# ST_LINK_V2.net
KiCad netlist of a schematic drawn in Altium Designer
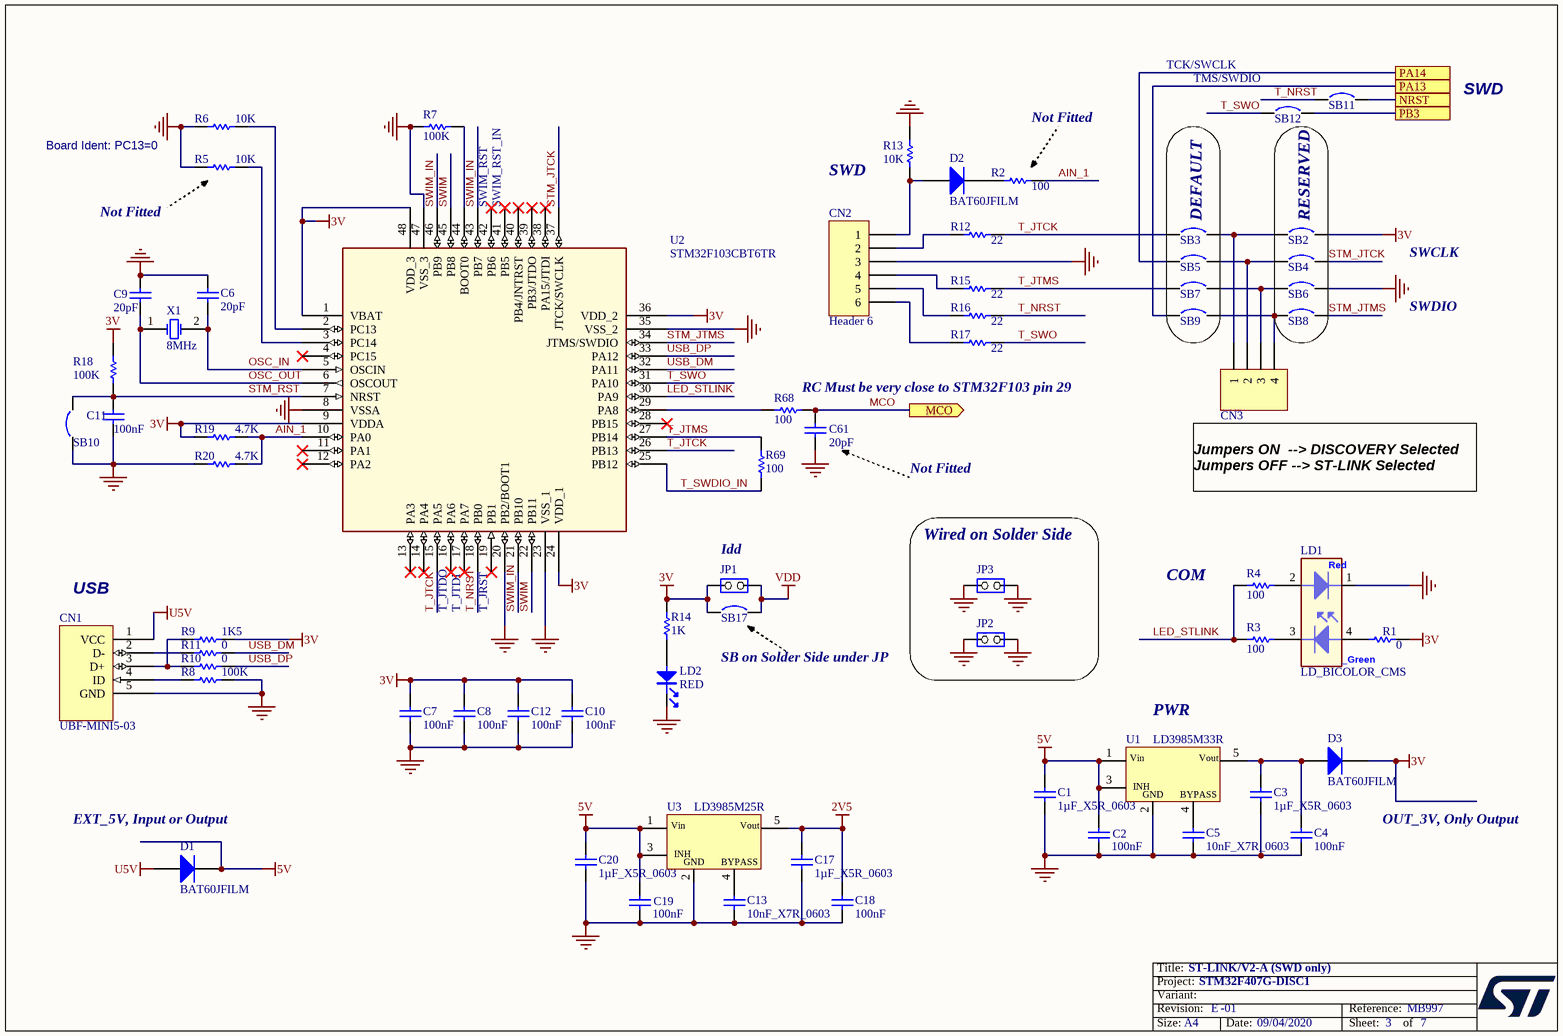
[diagram p0: ST_LINK_V2.SCHDOC]

(export (version "E")
  (design (tool "Eeschema 10.0.6"))
  (components
    (comp (ref "C1")
      (value "1µF_X5R_0603")
      (footprint "0603C")
      (description "0603  X5R 1µF")
      (fields (field (name "TOLERANCE") "10%"))
      (libsource (lib "MB963_1") (part "CAP SMD 0603  X5R 1µF 25V 10%"))
    )
    (comp (ref "C2")
      (value "100nF")
      (footprint "0402C")
      (description "Capacitor")
      (fields (field (name "PUBLISHER") "Altium Limited"))
      (libsource (lib "MB915_1") (part "Cap"))
    )
    (comp (ref "C3")
      (value "1µF_X5R_0603")
      (footprint "0603C")
      (description "0603  X5R 1µF")
      (fields (field (name "TOLERANCE") "10%"))
      (libsource (lib "MB963_1") (part "CAP SMD 0603  X5R 1µF 25V 10%"))
    )
    (comp (ref "C4")
      (value "100nF")
      (footprint "0402C")
      (description "Capacitor")
      (fields (field (name "PUBLISHER") "Altium Limited"))
      (libsource (lib "MB915_1") (part "Cap"))
    )
    (comp (ref "C5")
      (value "10nF_X7R_0603")
      (footprint "0603C")
      (description "0603  X7R 10NF")
      (fields (field (name "TOLERANCE") "10%"))
      (libsource (lib "MB963_1") (part "CAP SMD 0603  X7R 10000PF 50V 10%"))
    )
    (comp (ref "C6")
      (value "20pF")
      (footprint "0402C")
      (description "Capacitor")
      (fields (field (name "PUBLISHER") "Altium Limited"))
      (libsource (lib "MB915_1") (part "Cap"))
    )
    (comp (ref "C7")
      (value "100nF")
      (footprint "0402C")
      (description "Capacitor")
      (fields (field (name "PUBLISHER") "Altium Limited"))
      (libsource (lib "MB915_1") (part "Cap"))
    )
    (comp (ref "C8")
      (value "100nF")
      (footprint "0402C")
      (description "Capacitor")
      (fields (field (name "PUBLISHER") "Altium Limited"))
      (libsource (lib "MB915_1") (part "Cap"))
    )
    (comp (ref "C9")
      (value "20pF")
      (footprint "0402C")
      (description "Capacitor")
      (fields (field (name "PUBLISHER") "Altium Limited"))
      (libsource (lib "MB915_1") (part "Cap"))
    )
    (comp (ref "C10")
      (value "100nF")
      (footprint "0402C")
      (description "Capacitor")
      (fields (field (name "PUBLISHER") "Altium Limited"))
      (libsource (lib "MB915_1") (part "Cap"))
    )
    (comp (ref "C11")
      (value "100nF")
      (footprint "0402C")
      (description "Capacitor")
      (fields (field (name "PUBLISHER") "Altium Limited"))
      (libsource (lib "MB915_1") (part "Cap"))
    )
    (comp (ref "C12")
      (value "100nF")
      (footprint "0402C")
      (description "Capacitor")
      (fields (field (name "PUBLISHER") "Altium Limited"))
      (libsource (lib "MB915_1") (part "Cap"))
    )
    (comp (ref "C13")
      (value "10nF_X7R_0603")
      (footprint "0603C")
      (description "0603  X7R 10NF")
      (fields (field (name "TOLERANCE") "10%"))
      (libsource (lib "MB963_1") (part "CAP SMD 0603  X7R 10000PF 50V 10%"))
    )
    (comp (ref "C17")
      (value "1µF_X5R_0603")
      (footprint "0603C")
      (description "0603  X5R 1µF")
      (fields (field (name "TOLERANCE") "10%"))
      (libsource (lib "MB963_1") (part "CAP SMD 0603  X5R 1µF 25V 10%"))
    )
    (comp (ref "C18")
      (value "100nF")
      (footprint "0402C")
      (description "Capacitor")
      (fields (field (name "PUBLISHER") "Altium Limited"))
      (libsource (lib "MB915_1") (part "Cap"))
    )
    (comp (ref "C19")
      (value "100nF")
      (footprint "0402C")
      (description "Capacitor")
      (fields (field (name "PUBLISHER") "Altium Limited"))
      (libsource (lib "MB915_1") (part "Cap"))
    )
    (comp (ref "C20")
      (value "1µF_X5R_0603")
      (footprint "0603C")
      (description "0603  X5R 1µF")
      (fields (field (name "TOLERANCE") "10%"))
      (libsource (lib "MB963_1") (part "CAP SMD 0603  X5R 1µF 25V 10%"))
    )
    (comp (ref "C61")
      (value "20pF")
      (footprint "0603C")
      (description "Capacitor")
      (fields (field (name "PUBLISHER") "Altium Limited"))
      (libsource (lib "MB915_1") (part "Cap"))
    )
    (comp (ref "CN1")
      (value "UBF-MINI5-03")
      (footprint "USB-MINI-B-SMD-A_")
      (libsource (lib "MB997") (part "USB-MINI-typeB connector_"))
    )
    (comp (ref "CN2")
      (value "Header 6")
      (footprint "HEADER6$2F$2.54")
      (description "Header, 6-Pin")
      (fields (field (name "PUBLISHER") "Altium Limited"))
      (libsource (lib "Miscellaneous Connectors") (part "Header 6"))
    )
    (comp (ref "CN3")
      (value "Header 4")
      (footprint "HEADER4$2F$2.54")
      (description "Header, 4-Pin")
      (fields (field (name "PUBLISHER") "Altium Limited"))
      (libsource (lib "MB963_1") (part "Header 4"))
    )
    (comp (ref "D1")
      (value "BAT60JFILM")
      (footprint "SOD323$2F$A")
      (fields (field (name "PUBLISHER") "Altium Limited"))
      (libsource (lib "MB997") (part "BAT60JFILM"))
    )
    (comp (ref "D2")
      (value "BAT60JFILM")
      (footprint "SOD323$2F$A")
      (fields (field (name "PUBLISHER") "Altium Limited"))
      (libsource (lib "MB997") (part "BAT60JFILM"))
    )
    (comp (ref "D3")
      (value "BAT60JFILM")
      (footprint "SOD323$2F$A")
      (fields (field (name "PUBLISHER") "Altium Limited"))
      (libsource (lib "MB997") (part "BAT60JFILM"))
    )
    (comp (ref "JP1") (value "~") (footprint "SIP2$2F$2.54") (libsource (lib "*") (part "JP2")))
    (comp (ref "JP2") (value "~") (footprint "SIP2$2F$2.54") (libsource (lib "*") (part "JP2")))
    (comp (ref "JP3") (value "~") (footprint "SIP2$2F$2.54") (libsource (lib "*") (part "JP2")))
    (comp (ref "LD1")
      (value "LD_BICOLOR_CMS")
      (footprint "AV02-0501EN")
      (description "Bicolor Led")
      (libsource (lib "MB963") (part "LD_BICOLOR_CMS"))
    )
    (comp (ref "LD2") (value "RED") (footprint "LED0603") (libsource (lib "MB963_1") (part "PHOTO")))
    (comp (ref "R1")
      (value "0")
      (footprint "0603R")
      (description "Resistor")
      (fields (field (name "PUBLISHER") "Altium Limited"))
      (libsource (lib "MB915_1") (part "res1"))
    )
    (comp (ref "R2")
      (value "100")
      (footprint "0402R")
      (description "Resistor")
      (fields (field (name "PUBLISHER") "Altium Limited"))
      (libsource (lib "MB915_1") (part "res1"))
    )
    (comp (ref "R3")
      (value "100")
      (footprint "0402R")
      (description "Resistor")
      (fields (field (name "PUBLISHER") "Altium Limited"))
      (libsource (lib "MB915_1") (part "res1"))
    )
    (comp (ref "R4")
      (value "100")
      (footprint "0402R")
      (description "Resistor")
      (fields (field (name "PUBLISHER") "Altium Limited"))
      (libsource (lib "MB915_1") (part "res1"))
    )
    (comp (ref "R5")
      (value "10K")
      (footprint "0402R")
      (description "Resistor")
      (fields (field (name "PUBLISHER") "Altium Limited"))
      (libsource (lib "MB915_1") (part "res1"))
    )
    (comp (ref "R6")
      (value "10K")
      (footprint "0402R")
      (description "Resistor")
      (fields (field (name "PUBLISHER") "Altium Limited"))
      (libsource (lib "MB915_1") (part "res1"))
    )
    (comp (ref "R7")
      (value "100K")
      (footprint "0402R")
      (description "Resistor")
      (fields (field (name "PUBLISHER") "Altium Limited"))
      (libsource (lib "MB915_1") (part "res1"))
    )
    (comp (ref "R8")
      (value "100K")
      (footprint "0402R")
      (description "Resistor")
      (fields (field (name "PUBLISHER") "Altium Limited"))
      (libsource (lib "MB915_1") (part "res1"))
    )
    (comp (ref "R9")
      (value "1K5")
      (footprint "0402R")
      (description "Resistor")
      (fields (field (name "PUBLISHER") "Altium Limited"))
      (libsource (lib "MB915_1") (part "res1"))
    )
    (comp (ref "R10")
      (value "0")
      (footprint "0603R")
      (description "Resistor")
      (fields (field (name "PUBLISHER") "Altium Limited"))
      (libsource (lib "MB915_1") (part "res1"))
    )
    (comp (ref "R11")
      (value "0")
      (footprint "0603R")
      (description "Resistor")
      (fields (field (name "PUBLISHER") "Altium Limited"))
      (libsource (lib "MB915_1") (part "res1"))
    )
    (comp (ref "R12")
      (value "22")
      (footprint "0402R")
      (description "Resistor")
      (fields (field (name "PUBLISHER") "Altium Limited"))
      (libsource (lib "MB915_1") (part "res1"))
    )
    (comp (ref "R13")
      (value "10K")
      (footprint "0402R")
      (description "Resistor")
      (fields (field (name "PUBLISHER") "Altium Limited"))
      (libsource (lib "MB915_1") (part "res1"))
    )
    (comp (ref "R14")
      (value "1K")
      (footprint "0402R")
      (description "Resistor")
      (fields (field (name "PUBLISHER") "Altium Limited"))
      (libsource (lib "MB915_1") (part "res1"))
    )
    (comp (ref "R15")
      (value "22")
      (footprint "0402R")
      (description "Resistor")
      (fields (field (name "PUBLISHER") "Altium Limited"))
      (libsource (lib "MB915_1") (part "res1"))
    )
    (comp (ref "R16")
      (value "22")
      (footprint "0402R")
      (description "Resistor")
      (fields (field (name "PUBLISHER") "Altium Limited"))
      (libsource (lib "MB915_1") (part "res1"))
    )
    (comp (ref "R17")
      (value "22")
      (footprint "0402R")
      (description "Resistor")
      (fields (field (name "PUBLISHER") "Altium Limited"))
      (libsource (lib "MB915_1") (part "res1"))
    )
    (comp (ref "R18")
      (value "100K")
      (footprint "0402R")
      (description "Resistor")
      (fields (field (name "PUBLISHER") "Altium Limited"))
      (libsource (lib "MB915_1") (part "res1"))
    )
    (comp (ref "R19")
      (value "4.7K")
      (footprint "0402R")
      (description "Resistor")
      (fields (field (name "PUBLISHER") "Altium Limited"))
      (libsource (lib "MB915_1") (part "res1"))
    )
    (comp (ref "R20")
      (value "4.7K")
      (footprint "0402R")
      (description "Resistor")
      (fields (field (name "PUBLISHER") "Altium Limited"))
      (libsource (lib "MB915_1") (part "res1"))
    )
    (comp (ref "R68")
      (value "100")
      (footprint "0603R")
      (description "Resistor")
      (fields (field (name "PUBLISHER") "Altium Limited"))
      (libsource (lib "MB915_1") (part "res1"))
    )
    (comp (ref "R69")
      (value "100")
      (footprint "0402R")
      (description "Resistor")
      (fields (field (name "PUBLISHER") "Altium Limited"))
      (libsource (lib "MB915_1") (part "res1"))
    )
    (comp (ref "SB2")
      (value "Circuit Breaker")
      (footprint "JUMPER")
      (fields (field (name "PUBLISHER") "Altium Limited"))
      (libsource (lib "MB915") (part "Circuit Breaker"))
    )
    (comp (ref "SB3")
      (value "Circuit Breaker")
      (footprint "JUMPER")
      (fields (field (name "PUBLISHER") "Altium Limited"))
      (libsource (lib "MB915") (part "Circuit Breaker"))
    )
    (comp (ref "SB4")
      (value "Circuit Breaker")
      (footprint "JUMPER")
      (fields (field (name "PUBLISHER") "Altium Limited"))
      (libsource (lib "MB915") (part "Circuit Breaker"))
    )
    (comp (ref "SB5")
      (value "Circuit Breaker")
      (footprint "JUMPER")
      (fields (field (name "PUBLISHER") "Altium Limited"))
      (libsource (lib "MB915") (part "Circuit Breaker"))
    )
    (comp (ref "SB6")
      (value "Circuit Breaker")
      (footprint "JUMPER")
      (fields (field (name "PUBLISHER") "Altium Limited"))
      (libsource (lib "MB915") (part "Circuit Breaker"))
    )
    (comp (ref "SB7")
      (value "Circuit Breaker")
      (footprint "JUMPER")
      (fields (field (name "PUBLISHER") "Altium Limited"))
      (libsource (lib "MB915") (part "Circuit Breaker"))
    )
    (comp (ref "SB8")
      (value "Circuit Breaker")
      (footprint "JUMPER")
      (fields (field (name "PUBLISHER") "Altium Limited"))
      (libsource (lib "MB915") (part "Circuit Breaker"))
    )
    (comp (ref "SB9")
      (value "Circuit Breaker")
      (footprint "JUMPER")
      (fields (field (name "PUBLISHER") "Altium Limited"))
      (libsource (lib "MB915") (part "Circuit Breaker"))
    )
    (comp (ref "SB10")
      (value "Circuit Breaker")
      (footprint "JUMPER")
      (fields (field (name "PUBLISHER") "Altium Limited"))
      (libsource (lib "MB915") (part "Circuit Breaker"))
    )
    (comp (ref "SB11")
      (value "Circuit Breaker")
      (footprint "JUMPER")
      (fields (field (name "PUBLISHER") "Altium Limited"))
      (libsource (lib "MB915") (part "Circuit Breaker"))
    )
    (comp (ref "SB12")
      (value "Circuit Breaker")
      (footprint "JUMPER")
      (fields (field (name "PUBLISHER") "Altium Limited"))
      (libsource (lib "MB915") (part "Circuit Breaker"))
    )
    (comp (ref "SB17")
      (value "Circuit Breaker")
      (footprint "JUMPER")
      (fields (field (name "PUBLISHER") "Altium Limited"))
      (libsource (lib "MB915") (part "Circuit Breaker"))
    )
    (comp (ref "U1")
      (value "LD3985M33R")
      (footprint "SOT-23-5L")
      (description "Ultra low drop-low noise BiCMOS voltage, regulators low ESR capacitors compatible")
      (libsource (lib "MB997") (part "LD3985M33R"))
    )
    (comp (ref "U2")
      (value "STM32F103CBT6TR")
      (footprint "LQFP48$2F$0.5MM$5C$9X9B")
      (description "Medium-density performance line ARM-based 32-bit MCU with 128KB Flash")
      (libsource (lib "MCD_TOOLS") (part "STM32F103CBT6"))
    )
    (comp (ref "U3")
      (value "LD3985M25R")
      (footprint "SOT-23-5L")
      (description "Ultra low drop-low noise BiCMOS voltage, regulators low ESR capacitors compatible")
      (libsource (lib "MB997") (part "LD3985M25R"))
    )
    (comp (ref "X1")
      (value "8MHz")
      (footprint "HC-49A")
      (description "Crystal Oscillator")
      (fields (field (name "PUBLISHER") "Altium Limited"))
      (libsource (lib "MB963_1") (part "XTAL"))
    )
  )
  (nets
    (net (code "1") (name "/AIN_1") (class "Default")
      (node (ref "R19") (pin "2") (pinfunction "2_2") (pintype "passive"))
      (node (ref "R2") (pin "2") (pinfunction "2_2") (pintype "passive"))
      (node (ref "R20") (pin "2") (pinfunction "2_2") (pintype "passive"))
      (node (ref "U2") (pin "10") (pinfunction "PA0_10") (pintype "bidirectional"))
    )
    (net (code "2") (name "/LED_STLINK") (class "Default")
      (node (ref "R3") (pin "1") (pinfunction "1_1") (pintype "passive"))
      (node (ref "R4") (pin "1") (pinfunction "1_1") (pintype "passive"))
      (node (ref "U2") (pin "30") (pinfunction "PA9_30") (pintype "bidirectional"))
    )
    (net (code "3") (name "/MCO") (class "Default")
      (node (ref "C61") (pin "1") (pinfunction "1_1") (pintype "passive"))
      (node (ref "R68") (pin "2") (pinfunction "2_2") (pintype "passive"))
    )
    (net (code "4") (name "/NRST") (class "Default")
      (node (ref "SB11") (pin "2") (pinfunction "2_2") (pintype "passive"))
    )
    (net (code "5") (name "/OSC_IN") (class "Default")
      (node (ref "C6") (pin "2") (pinfunction "2_2") (pintype "passive"))
      (node (ref "U2") (pin "5") (pinfunction "OSCIN_5") (pintype "input"))
      (node (ref "X1") (pin "2") (pinfunction "OSC2_2") (pintype "passive"))
    )
    (net (code "6") (name "/OSC_OUT") (class "Default")
      (node (ref "C9") (pin "2") (pinfunction "2_2") (pintype "passive"))
      (node (ref "U2") (pin "6") (pinfunction "OSCOUT_6") (pintype "output"))
      (node (ref "X1") (pin "1") (pinfunction "OSC1_1") (pintype "passive"))
    )
    (net (code "7") (name "/PA13") (class "Default")
      (node (ref "SB9") (pin "1") (pinfunction "1_1") (pintype "passive"))
    )
    (net (code "8") (name "/PA14") (class "Default")
      (node (ref "SB5") (pin "1") (pinfunction "1_1") (pintype "passive"))
    )
    (net (code "9") (name "/PB3") (class "Default")
      (node (ref "SB12") (pin "2") (pinfunction "2_2") (pintype "passive"))
    )
    (net (code "10") (name "/STM_JTCK") (class "Default")
      (node (ref "SB4") (pin "2") (pinfunction "2_2") (pintype "passive"))
      (node (ref "U2") (pin "37") (pinfunction "JTCK/SWCLK_37") (pintype "bidirectional"))
    )
    (net (code "11") (name "/STM_JTMS") (class "Default")
      (node (ref "SB8") (pin "2") (pinfunction "2_2") (pintype "passive"))
      (node (ref "U2") (pin "34") (pinfunction "JTMS/SWDIO_34") (pintype "bidirectional"))
    )
    (net (code "12") (name "/STM_RST") (class "Default")
      (node (ref "C11") (pin "2") (pinfunction "2_2") (pintype "passive"))
      (node (ref "R18") (pin "1") (pinfunction "1_1") (pintype "passive"))
      (node (ref "SB10") (pin "2") (pinfunction "2_2") (pintype "passive"))
      (node (ref "U2") (pin "7") (pinfunction "NRST_7") (pintype "input"))
    )
    (net (code "13") (name "/SWIM") (class "Default")
      (node (ref "U2") (pin "22") (pinfunction "PB11_22") (pintype "bidirectional"))
      (node (ref "U2") (pin "45") (pinfunction "PB8_45") (pintype "bidirectional"))
    )
    (net (code "14") (name "/SWIM_IN") (class "Default")
      (node (ref "U2") (pin "21") (pinfunction "PB10_21") (pintype "bidirectional"))
      (node (ref "U2") (pin "43") (pinfunction "PB7_43") (pintype "bidirectional"))
      (node (ref "U2") (pin "46") (pinfunction "PB9_46") (pintype "bidirectional"))
    )
    (net (code "15") (name "/T_JTCK") (class "Default")
      (node (ref "R12") (pin "2") (pinfunction "2_2") (pintype "passive"))
      (node (ref "SB3") (pin "1") (pinfunction "1_1") (pintype "passive"))
      (node (ref "U2") (pin "15") (pinfunction "PA5_15") (pintype "bidirectional"))
      (node (ref "U2") (pin "26") (pinfunction "PB13_26") (pintype "bidirectional"))
    )
    (net (code "16") (name "/T_JTMS") (class "Default")
      (node (ref "R15") (pin "2") (pinfunction "2_2") (pintype "passive"))
      (node (ref "R69") (pin "2") (pinfunction "2_2") (pintype "passive"))
      (node (ref "SB7") (pin "1") (pinfunction "1_1") (pintype "passive"))
      (node (ref "U2") (pin "27") (pinfunction "PB14_27") (pintype "bidirectional"))
    )
    (net (code "17") (name "/T_NRST") (class "Default")
      (node (ref "R16") (pin "2") (pinfunction "2_2") (pintype "passive"))
      (node (ref "SB11") (pin "1") (pinfunction "1_1") (pintype "passive"))
      (node (ref "U2") (pin "18") (pinfunction "PB0_18") (pintype "bidirectional"))
    )
    (net (code "18") (name "/T_SWDIO_IN") (class "Default")
      (node (ref "R69") (pin "1") (pinfunction "1_1") (pintype "passive"))
      (node (ref "U2") (pin "25") (pinfunction "PB12_25") (pintype "bidirectional"))
    )
    (net (code "19") (name "/T_SWO") (class "Default")
      (node (ref "R17") (pin "2") (pinfunction "2_2") (pintype "passive"))
      (node (ref "SB12") (pin "1") (pinfunction "1_1") (pintype "passive"))
      (node (ref "U2") (pin "31") (pinfunction "PA10_31") (pintype "bidirectional"))
    )
    (net (code "20") (name "/USB_DM") (class "Default")
      (node (ref "R11") (pin "2") (pinfunction "2_2") (pintype "passive"))
      (node (ref "U2") (pin "32") (pinfunction "PA11_32") (pintype "bidirectional"))
    )
    (net (code "21") (name "/USB_DP") (class "Default")
      (node (ref "R10") (pin "2") (pinfunction "2_2") (pintype "passive"))
      (node (ref "U2") (pin "33") (pinfunction "PA12_33") (pintype "bidirectional"))
    )
    (net (code "22") (name "2V5") (class "Default")
      (node (ref "C17") (pin "1") (pinfunction "1_1") (pintype "passive"))
      (node (ref "C18") (pin "2") (pinfunction "2_2") (pintype "passive"))
      (node (ref "U3") (pin "5") (pinfunction "Vout_5") (pintype "passive"))
    )
    (net (code "23") (name "3V") (class "Default")
      (node (ref "C10") (pin "2") (pinfunction "2_2") (pintype "passive"))
      (node (ref "C12") (pin "1") (pinfunction "1_1") (pintype "passive"))
      (node (ref "C7") (pin "2") (pinfunction "2_2") (pintype "passive"))
      (node (ref "C8") (pin "2") (pinfunction "2_2") (pintype "passive"))
      (node (ref "D3") (pin "2") (pinfunction "K_2") (pintype "passive"))
      (node (ref "JP1") (pin "1") (pinfunction "COMMON_1") (pintype "passive"))
      (node (ref "R1") (pin "2") (pinfunction "2_2") (pintype "passive"))
      (node (ref "R14") (pin "2") (pinfunction "2_2") (pintype "passive"))
      (node (ref "R18") (pin "2") (pinfunction "2_2") (pintype "passive"))
      (node (ref "R19") (pin "1") (pinfunction "1_1") (pintype "passive"))
      (node (ref "R9") (pin "2") (pinfunction "2_2") (pintype "passive"))
      (node (ref "SB17") (pin "1") (pinfunction "1_1") (pintype "passive"))
      (node (ref "SB2") (pin "2") (pinfunction "2_2") (pintype "passive"))
      (node (ref "U2") (pin "1") (pinfunction "VBAT_1") (pintype "power_in"))
      (node (ref "U2") (pin "24") (pinfunction "VDD_1_24") (pintype "power_in"))
      (node (ref "U2") (pin "36") (pinfunction "VDD_2_36") (pintype "power_in"))
      (node (ref "U2") (pin "48") (pinfunction "VDD_3_48") (pintype "power_in"))
      (node (ref "U2") (pin "9") (pinfunction "VDDA_9") (pintype "power_in"))
    )
    (net (code "24") (name "5V") (class "Default")
      (node (ref "C1") (pin "2") (pinfunction "2_2") (pintype "passive"))
      (node (ref "C19") (pin "2") (pinfunction "2_2") (pintype "passive"))
      (node (ref "C2") (pin "2") (pinfunction "2_2") (pintype "passive"))
      (node (ref "C20") (pin "2") (pinfunction "2_2") (pintype "passive"))
      (node (ref "D1") (pin "2") (pinfunction "K_2") (pintype "passive"))
      (node (ref "U1") (pin "1") (pinfunction "Vin_1") (pintype "passive"))
      (node (ref "U1") (pin "3") (pinfunction "CE_3") (pintype "passive"))
      (node (ref "U3") (pin "1") (pinfunction "Vin_1") (pintype "passive"))
      (node (ref "U3") (pin "3") (pinfunction "CE_3") (pintype "passive"))
    )
    (net (code "25") (name "GND") (class "Default")
      (node (ref "C1") (pin "1") (pinfunction "1_1") (pintype "passive"))
      (node (ref "C10") (pin "1") (pinfunction "1_1") (pintype "passive"))
      (node (ref "C11") (pin "1") (pinfunction "1_1") (pintype "passive"))
      (node (ref "C12") (pin "2") (pinfunction "2_2") (pintype "passive"))
      (node (ref "C13") (pin "1") (pinfunction "1_1") (pintype "passive"))
      (node (ref "C17") (pin "2") (pinfunction "2_2") (pintype "passive"))
      (node (ref "C18") (pin "1") (pinfunction "1_1") (pintype "passive"))
      (node (ref "C19") (pin "1") (pinfunction "1_1") (pintype "passive"))
      (node (ref "C2") (pin "1") (pinfunction "1_1") (pintype "passive"))
      (node (ref "C20") (pin "1") (pinfunction "1_1") (pintype "passive"))
      (node (ref "C3") (pin "2") (pinfunction "2_2") (pintype "passive"))
      (node (ref "C4") (pin "1") (pinfunction "1_1") (pintype "passive"))
      (node (ref "C5") (pin "1") (pinfunction "1_1") (pintype "passive"))
      (node (ref "C6") (pin "1") (pinfunction "1_1") (pintype "passive"))
      (node (ref "C61") (pin "2") (pinfunction "2_2") (pintype "passive"))
      (node (ref "C7") (pin "1") (pinfunction "1_1") (pintype "passive"))
      (node (ref "C8") (pin "1") (pinfunction "1_1") (pintype "passive"))
      (node (ref "C9") (pin "1") (pinfunction "1_1") (pintype "passive"))
      (node (ref "CN1") (pin "5") (pinfunction "GND_5") (pintype "power_in"))
      (node (ref "CN2") (pin "3") (pinfunction "3_3") (pintype "passive"))
      (node (ref "JP2") (pin "1") (pinfunction "COMMON_1") (pintype "passive"))
      (node (ref "JP2") (pin "2") (pinfunction "NO_2") (pintype "passive"))
      (node (ref "JP3") (pin "1") (pinfunction "COMMON_1") (pintype "passive"))
      (node (ref "JP3") (pin "2") (pinfunction "NO_2") (pintype "passive"))
      (node (ref "LD1") (pin "1") (pinfunction "1_1") (pintype "passive"))
      (node (ref "LD2") (pin "2") (pintype "passive"))
      (node (ref "R13") (pin "2") (pinfunction "2_2") (pintype "passive"))
      (node (ref "R20") (pin "1") (pinfunction "1_1") (pintype "passive"))
      (node (ref "R5") (pin "1") (pinfunction "1_1") (pintype "passive"))
      (node (ref "R6") (pin "1") (pinfunction "1_1") (pintype "passive"))
      (node (ref "R7") (pin "1") (pinfunction "1_1") (pintype "passive"))
      (node (ref "R8") (pin "2") (pinfunction "2_2") (pintype "passive"))
      (node (ref "SB10") (pin "1") (pinfunction "1_1") (pintype "passive"))
      (node (ref "SB6") (pin "2") (pinfunction "2_2") (pintype "passive"))
      (node (ref "U1") (pin "2") (pinfunction "GND_2") (pintype "passive"))
      (node (ref "U2") (pin "20") (pinfunction "PB2/BOOT1_20") (pintype "bidirectional"))
      (node (ref "U2") (pin "23") (pinfunction "VSS_1_23") (pintype "power_in"))
      (node (ref "U2") (pin "35") (pinfunction "VSS_2_35") (pintype "power_in"))
      (node (ref "U2") (pin "47") (pinfunction "VSS_3_47") (pintype "power_in"))
      (node (ref "U2") (pin "8") (pinfunction "VSSA_8") (pintype "power_in"))
      (node (ref "U3") (pin "2") (pinfunction "GND_2") (pintype "passive"))
    )
    (net (code "26") (name "Net-(CN1-D+)") (class "Default")
      (node (ref "CN1") (pin "3") (pinfunction "D+_3") (pintype "bidirectional"))
      (node (ref "R10") (pin "1") (pinfunction "1_1") (pintype "passive"))
      (node (ref "R9") (pin "1") (pinfunction "1_1") (pintype "passive"))
    )
    (net (code "27") (name "Net-(CN1-D-)") (class "Default")
      (node (ref "CN1") (pin "2") (pinfunction "D-_2") (pintype "bidirectional"))
      (node (ref "R11") (pin "1") (pinfunction "1_1") (pintype "passive"))
    )
    (net (code "28") (name "Net-(CN1-ID)") (class "Default")
      (node (ref "CN1") (pin "4") (pinfunction "ID_4") (pintype "input"))
      (node (ref "R8") (pin "1") (pinfunction "1_1") (pintype "passive"))
    )
    (net (code "29") (name "Net-(CN2-Pad2)") (class "Default")
      (node (ref "CN2") (pin "2") (pinfunction "2_2") (pintype "passive"))
      (node (ref "R12") (pin "1") (pinfunction "1_1") (pintype "passive"))
    )
    (net (code "30") (name "Net-(CN2-Pad4)") (class "Default")
      (node (ref "CN2") (pin "4") (pinfunction "4_4") (pintype "passive"))
      (node (ref "R15") (pin "1") (pinfunction "1_1") (pintype "passive"))
    )
    (net (code "31") (name "Net-(CN2-Pad5)") (class "Default")
      (node (ref "CN2") (pin "5") (pinfunction "5_5") (pintype "passive"))
      (node (ref "R16") (pin "1") (pinfunction "1_1") (pintype "passive"))
    )
    (net (code "32") (name "Net-(CN2-Pad6)") (class "Default")
      (node (ref "CN2") (pin "6") (pinfunction "6_6") (pintype "passive"))
      (node (ref "R17") (pin "1") (pinfunction "1_1") (pintype "passive"))
    )
    (net (code "33") (name "Net-(CN3-Pad1)") (class "Default")
      (node (ref "CN3") (pin "1") (pinfunction "1_1") (pintype "passive"))
      (node (ref "SB2") (pin "1") (pinfunction "1_1") (pintype "passive"))
      (node (ref "SB3") (pin "2") (pinfunction "2_2") (pintype "passive"))
    )
    (net (code "34") (name "Net-(CN3-Pad2)") (class "Default")
      (node (ref "CN3") (pin "2") (pinfunction "2_2") (pintype "passive"))
      (node (ref "SB4") (pin "1") (pinfunction "1_1") (pintype "passive"))
      (node (ref "SB5") (pin "2") (pinfunction "2_2") (pintype "passive"))
    )
    (net (code "35") (name "Net-(CN3-Pad3)") (class "Default")
      (node (ref "CN3") (pin "3") (pinfunction "3_3") (pintype "passive"))
      (node (ref "SB6") (pin "1") (pinfunction "1_1") (pintype "passive"))
      (node (ref "SB7") (pin "2") (pinfunction "2_2") (pintype "passive"))
    )
    (net (code "36") (name "Net-(CN3-Pad4)") (class "Default")
      (node (ref "CN3") (pin "4") (pinfunction "4_4") (pintype "passive"))
      (node (ref "SB8") (pin "1") (pinfunction "1_1") (pintype "passive"))
      (node (ref "SB9") (pin "2") (pinfunction "2_2") (pintype "passive"))
    )
    (net (code "37") (name "Net-(D2-A)") (class "Default")
      (node (ref "CN2") (pin "1") (pinfunction "1_1") (pintype "passive"))
      (node (ref "D2") (pin "1") (pinfunction "A_1") (pintype "passive"))
      (node (ref "R13") (pin "1") (pinfunction "1_1") (pintype "passive"))
    )
    (net (code "38") (name "Net-(D2-K)") (class "Default")
      (node (ref "D2") (pin "2") (pinfunction "K_2") (pintype "passive"))
      (node (ref "R2") (pin "1") (pinfunction "1_1") (pintype "passive"))
    )
    (net (code "39") (name "Net-(D3-A)") (class "Default")
      (node (ref "C3") (pin "1") (pinfunction "1_1") (pintype "passive"))
      (node (ref "C4") (pin "2") (pinfunction "2_2") (pintype "passive"))
      (node (ref "D3") (pin "1") (pinfunction "A_1") (pintype "passive"))
      (node (ref "U1") (pin "5") (pinfunction "Vout_5") (pintype "passive"))
    )
    (net (code "40") (name "Net-(LD1-Pad2)") (class "Default")
      (node (ref "LD1") (pin "2") (pinfunction "2_2") (pintype "passive"))
      (node (ref "R4") (pin "2") (pinfunction "2_2") (pintype "passive"))
    )
    (net (code "41") (name "Net-(LD1-Pad3)") (class "Default")
      (node (ref "LD1") (pin "3") (pinfunction "3_3") (pintype "passive"))
      (node (ref "R3") (pin "2") (pinfunction "2_2") (pintype "passive"))
    )
    (net (code "42") (name "Net-(LD1-Pad4)") (class "Default")
      (node (ref "LD1") (pin "4") (pinfunction "4_4") (pintype "passive"))
      (node (ref "R1") (pin "1") (pinfunction "1_1") (pintype "passive"))
    )
    (net (code "43") (name "Net-(LD2-Pad1)") (class "Default")
      (node (ref "LD2") (pin "1") (pintype "passive"))
      (node (ref "R14") (pin "1") (pinfunction "1_1") (pintype "passive"))
    )
    (net (code "44") (name "Net-(U1-BYPASS)") (class "Default")
      (node (ref "C5") (pin "2") (pinfunction "2_2") (pintype "passive"))
      (node (ref "U1") (pin "4") (pinfunction "BYPASS_4") (pintype "passive"))
    )
    (net (code "45") (name "Net-(U2-BOOT0)") (class "Default")
      (node (ref "R7") (pin "2") (pinfunction "2_2") (pintype "passive"))
      (node (ref "U2") (pin "44") (pinfunction "BOOT0_44") (pintype "bidirectional"))
    )
    (net (code "46") (name "Net-(U2-PA8)") (class "Default")
      (node (ref "R68") (pin "1") (pinfunction "1_1") (pintype "passive"))
      (node (ref "U2") (pin "29") (pinfunction "PA8_29") (pintype "bidirectional"))
    )
    (net (code "47") (name "Net-(U2-PC13)") (class "Default")
      (node (ref "R6") (pin "2") (pinfunction "2_2") (pintype "passive"))
      (node (ref "U2") (pin "2") (pinfunction "PC13_2") (pintype "bidirectional"))
    )
    (net (code "48") (name "Net-(U2-PC14)") (class "Default")
      (node (ref "R5") (pin "2") (pinfunction "2_2") (pintype "passive"))
      (node (ref "U2") (pin "3") (pinfunction "PC14_3") (pintype "bidirectional"))
    )
    (net (code "49") (name "Net-(U3-BYPASS)") (class "Default")
      (node (ref "C13") (pin "2") (pinfunction "2_2") (pintype "passive"))
      (node (ref "U3") (pin "4") (pinfunction "BYPASS_4") (pintype "passive"))
    )
    (net (code "50") (name "U5V") (class "Default")
      (node (ref "CN1") (pin "1") (pinfunction "VCC_1") (pintype "power_in"))
      (node (ref "D1") (pin "1") (pinfunction "A_1") (pintype "passive"))
    )
    (net (code "51") (name "VDD") (class "Default")
      (node (ref "JP1") (pin "2") (pinfunction "NO_2") (pintype "passive"))
      (node (ref "SB17") (pin "2") (pinfunction "2_2") (pintype "passive"))
    )
    (net (code "52") (name "unconnected-(U2-PA1-Pad11)") (class "Default")
      (node (ref "U2") (pin "11") (pinfunction "PA1_11") (pintype "bidirectional+no_connect"))
    )
    (net (code "53") (name "unconnected-(U2-PA2-Pad12)") (class "Default")
      (node (ref "U2") (pin "12") (pinfunction "PA2_12") (pintype "bidirectional+no_connect"))
    )
    (net (code "54") (name "unconnected-(U2-PA3-Pad13)") (class "Default")
      (node (ref "U2") (pin "13") (pinfunction "PA3_13") (pintype "bidirectional+no_connect"))
    )
    (net (code "55") (name "unconnected-(U2-PA4-Pad14)") (class "Default")
      (node (ref "U2") (pin "14") (pinfunction "PA4_14") (pintype "bidirectional+no_connect"))
    )
    (net (code "56") (name "unconnected-(U2-PA6-Pad16)") (class "Default")
      (node (ref "U2") (pin "16") (pinfunction "PA6_16") (pintype "bidirectional+no_connect"))
    )
    (net (code "57") (name "unconnected-(U2-PA7-Pad17)") (class "Default")
      (node (ref "U2") (pin "17") (pinfunction "PA7_17") (pintype "bidirectional+no_connect"))
    )
    (net (code "58") (name "unconnected-(U2-PA15{slash}JTDI-Pad38)") (class "Default")
      (node (ref "U2") (pin "38") (pinfunction "PA15/JTDI_38") (pintype "bidirectional+no_connect"))
    )
    (net (code "59") (name "unconnected-(U2-PB1-Pad19)") (class "Default")
      (node (ref "U2") (pin "19") (pinfunction "PB1_19") (pintype "input+no_connect"))
    )
    (net (code "60") (name "unconnected-(U2-PB3{slash}JTDO-Pad39)") (class "Default")
      (node (ref "U2") (pin "39") (pinfunction "PB3/JTDO_39") (pintype "bidirectional+no_connect"))
    )
    (net (code "61") (name "unconnected-(U2-PB4{slash}JNTRST-Pad40)") (class "Default")
      (node (ref "U2") (pin "40") (pinfunction "PB4/JNTRST_40") (pintype "bidirectional+no_connect"))
    )
    (net (code "62") (name "unconnected-(U2-PB5-Pad41)") (class "Default")
      (node (ref "U2") (pin "41") (pinfunction "PB5_41") (pintype "bidirectional+no_connect"))
    )
    (net (code "63") (name "unconnected-(U2-PB6-Pad42)") (class "Default")
      (node (ref "U2") (pin "42") (pinfunction "PB6_42") (pintype "bidirectional+no_connect"))
    )
    (net (code "64") (name "unconnected-(U2-PB15-Pad28)") (class "Default")
      (node (ref "U2") (pin "28") (pinfunction "PB15_28") (pintype "bidirectional+no_connect"))
    )
    (net (code "65") (name "unconnected-(U2-PC15-Pad4)") (class "Default")
      (node (ref "U2") (pin "4") (pinfunction "PC15_4") (pintype "bidirectional+no_connect"))
    )
  )
)
